# IO_PWR_FMU3_REV_G.net
KiCad netlist of a schematic drawn in Altium Designer
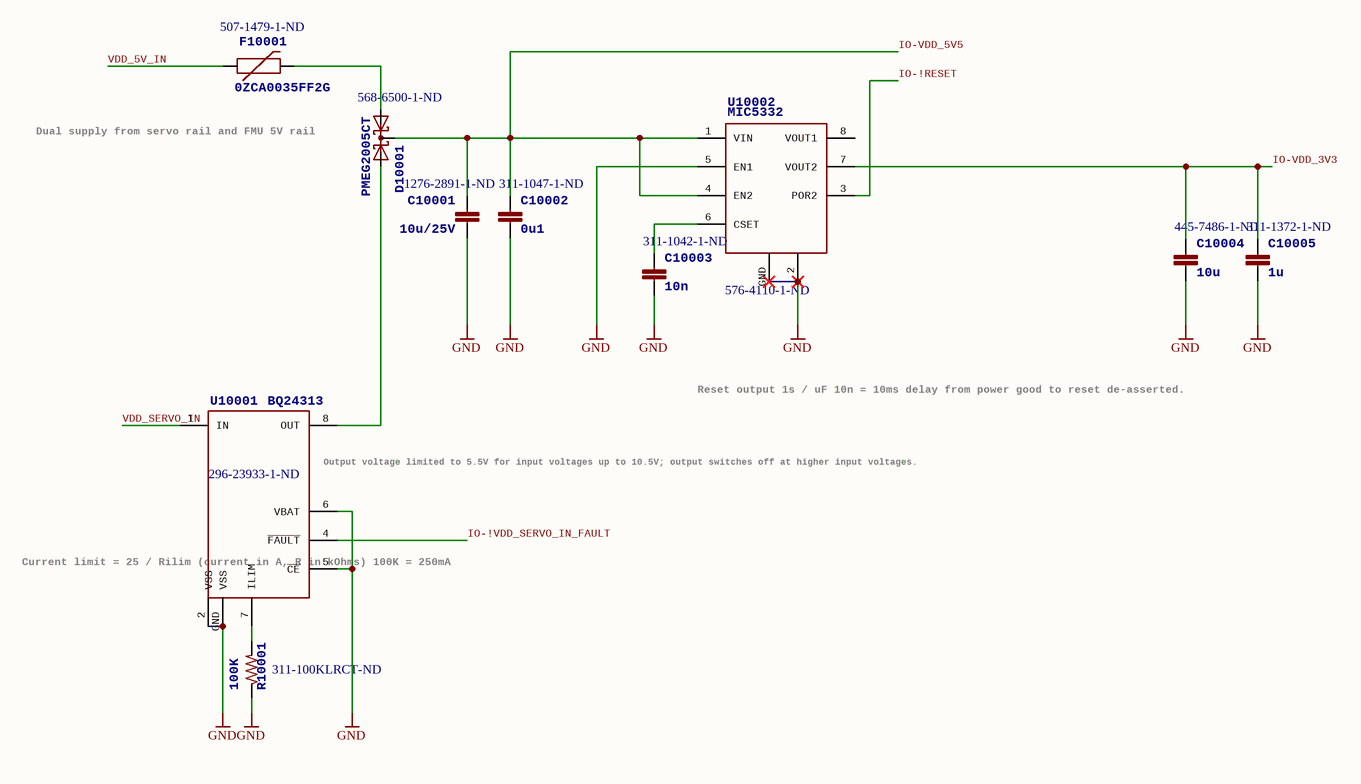
[diagram p0: IO_PWR_FMU3_REV_G.SchDoc]

(export (version "E")
  (design (tool "Eeschema 10.0.6"))
  (components
    (comp (ref "C10001")
      (value "10u/25V")
      (footprint "0805-CAP")
      (description "CAP CER 10UF 25V 10% X5R 0805")
      (fields
        (field (name "PARTNO") "CL21A106KAYNNNE")
        (field (name "SUPPLIER PART NUMBER 1") "1276-2891-1-ND")
        (field (name "3DR_PARTNO") "ECM0714")
      )
      (libsource (lib "pixhawk2") (part "CAP0805"))
    )
    (comp (ref "C10002")
      (value "0u1")
      (footprint "0402-CAP")
      (description "CAP CER 0.1UF 16V Y5V 0402")
      (fields
        (field (name "PARTNO") "CC0402ZRY5V7BB104")
        (field (name "SUPPLIER PART NUMBER 1") "311-1047-1-ND")
        (field (name "3DR_PARTNO") "ECM0700")
      )
      (libsource (lib "pixhawk2") (part "CAP0402"))
    )
    (comp (ref "C10003")
      (value "10n")
      (footprint "0402-CAP")
      (description "CAP CER 10000PF 16V 10% X7R 0402")
      (fields
        (field (name "PARTNO") "CC0402KRX7R7BB103")
        (field (name "SUPPLIER PART NUMBER 1") "311-1042-1-ND")
        (field (name "3DR_PARTNO") "ECM0711")
      )
      (libsource (lib "pixhawk2") (part "CAP0402"))
    )
    (comp (ref "C10004")
      (value "10u")
      (footprint "0603-CAP")
      (description "CAP CER 10UF 10V 10% X5R 0603")
      (fields
        (field (name "PARTNO") "C1608X5R1A106K080AC")
        (field (name "SUPPLIER PART NUMBER 1") "445-7486-1-ND")
        (field (name "3DR_PARTNO") "ECM0712")
      )
      (libsource (lib "pixhawk2") (part "CAP0603"))
    )
    (comp (ref "C10005")
      (value "1u")
      (footprint "0603-CAP")
      (description "CAP CER 1UF 16V Y5V 0603")
      (fields
        (field (name "PARTNO") "CC0603ZRY5V7BB105")
        (field (name "SUPPLIER PART NUMBER 1") "311-1372-1-ND")
        (field (name "3DR_PARTNO") "ECM0705")
      )
      (libsource (lib "pixhawk2") (part "CAP0603"))
    )
    (comp (ref "D10001")
      (value "PMEG2005CT")
      (footprint "SOT23-3")
      (description "DIODE SCHOTTKY 20V 500MA TO236AB")
      (fields (field (name "SUPPLIER PART NUMBER 1") "568-6500-1-ND") (field (name "3DR_PARTNO") "ECM0838"))
      (libsource (lib "pixhawk2") (part "PMEG2005CT"))
    )
    (comp (ref "F10001")
      (value "0ZCA0035FF2G")
      (footprint "PTC-1206")
      (description "PTC RESTTBLE 0.35A 16V CHIP 1206")
      (fields (field (name "SUPPLIER PART NUMBER 1") "507-1479-1-ND") (field (name "3DR_PARTNO") "ECM0802"))
      (libsource (lib "pixhawk2") (part "PTCSMD"))
    )
    (comp (ref "R10001")
      (value "100K")
      (footprint "0402-RES")
      (description "RES 100K OHM 1/16W 1% 0402 SMD")
      (fields
        (field (name "SUPPLIER PART NUMBER 1") "311-100KLRCT-ND")
        (field (name "3DR_PARTNO") "ECM0818")
        (field (name "PARTNO") "RC0402FR-07100KL")
      )
      (libsource (lib "pixhawk2") (part "RESISTOR0402-RES"))
    )
    (comp (ref "U10001")
      (value "BQ24313")
      (footprint "QFN8-DSG")
      (description "IC LI+ CHARGER FRONT END 8-SON")
      (fields
        (field (name "SUPPLIER PART NUMBER 1") "296-23933-1-ND")
        (field (name "3DR_PARTNO") "ECM0824")
        (field (name "PARTNO") "BQ24313DSGT")
      )
      (libsource (lib "pixhawk2") (part "BQ24313"))
    )
    (comp (ref "U10002")
      (value "MIC5332")
      (footprint "MLF-8-EPAD")
      (description "IC REG LDO 3.3V 0.3A 8TMLF")
      (fields
        (field (name "SUPPLIER PART NUMBER 1") "576-4110-1-ND")
        (field (name "3DR_PARTNO") "ECM0832")
        (field (name "PARTNO") "MIC5332-SSYMT TR")
      )
      (libsource (lib "pixhawk2") (part "MIC5332"))
    )
  )
  (nets
    (net (code "1") (name "/IO-!RESET") (class "Default")
      (node (ref "U10002") (pin "3") (pinfunction "POR2_3") (pintype "passive"))
    )
    (net (code "2") (name "/IO-!VDD_SERVO_IN_FAULT") (class "Default")
      (node (ref "U10001") (pin "4") (pinfunction "~{FAULT}_4") (pintype "passive"))
    )
    (net (code "3") (name "/IO-VDD_3V3") (class "Default")
      (node (ref "C10004") (pin "P$1") (pinfunction "1_P$1") (pintype "passive"))
      (node (ref "C10005") (pin "P$1") (pinfunction "1_P$1") (pintype "passive"))
      (node (ref "U10002") (pin "7") (pinfunction "VOUT2_7") (pintype "passive"))
    )
    (net (code "4") (name "/IO-VDD_5V5") (class "Default")
      (node (ref "C10001") (pin "P$1") (pinfunction "1_P$1") (pintype "passive"))
      (node (ref "C10002") (pin "P$1") (pinfunction "1_P$1") (pintype "passive"))
      (node (ref "D10001") (pin "3") (pinfunction "CC_3") (pintype "passive"))
      (node (ref "U10002") (pin "1") (pinfunction "VIN_1") (pintype "passive"))
      (node (ref "U10002") (pin "4") (pinfunction "EN2_4") (pintype "passive"))
    )
    (net (code "5") (name "/VDD_5V_IN") (class "Default")
      (node (ref "F10001") (pin "1") (pinfunction "1_1") (pintype "passive"))
    )
    (net (code "6") (name "/VDD_SERVO_IN") (class "Default")
      (node (ref "U10001") (pin "1") (pinfunction "IN_1") (pintype "passive"))
    )
    (net (code "7") (name "GND") (class "Default")
      (node (ref "C10001") (pin "P$2") (pinfunction "2_P$2") (pintype "passive"))
      (node (ref "C10002") (pin "P$2") (pinfunction "2_P$2") (pintype "passive"))
      (node (ref "C10003") (pin "P$2") (pinfunction "2_P$2") (pintype "passive"))
      (node (ref "C10004") (pin "P$2") (pinfunction "2_P$2") (pintype "passive"))
      (node (ref "C10005") (pin "P$2") (pinfunction "2_P$2") (pintype "passive"))
      (node (ref "R10001") (pin "P$1") (pinfunction "1_P$1") (pintype "passive"))
      (node (ref "U10001") (pin "2") (pinfunction "VSS_2") (pintype "passive"))
      (node (ref "U10001") (pin "5") (pinfunction "~{CE}_5") (pintype "passive"))
      (node (ref "U10001") (pin "6") (pinfunction "VBAT_6") (pintype "passive"))
      (node (ref "U10001") (pin "GND") (pinfunction "VSS_GND") (pintype "passive"))
      (node (ref "U10002") (pin "2") (pinfunction "GND_2") (pintype "power_in"))
      (node (ref "U10002") (pin "5") (pinfunction "EN1_5") (pintype "passive"))
      (node (ref "U10002") (pin "GND") (pinfunction "GND_GND") (pintype "power_in"))
    )
    (net (code "8") (name "Net-(C10003-1)") (class "Default")
      (node (ref "C10003") (pin "P$1") (pinfunction "1_P$1") (pintype "passive"))
      (node (ref "U10002") (pin "6") (pinfunction "CSET_6") (pintype "passive"))
    )
    (net (code "9") (name "Net-(D10001-A1)") (class "Default")
      (node (ref "D10001") (pin "1") (pinfunction "A1_1") (pintype "passive"))
      (node (ref "F10001") (pin "2") (pinfunction "2_2") (pintype "passive"))
    )
    (net (code "10") (name "Net-(D10001-A2)") (class "Default")
      (node (ref "D10001") (pin "2") (pinfunction "A2_2") (pintype "passive"))
      (node (ref "U10001") (pin "8") (pinfunction "OUT_8") (pintype "passive"))
    )
    (net (code "11") (name "Net-(R10001-2)") (class "Default")
      (node (ref "R10001") (pin "P$2") (pinfunction "2_P$2") (pintype "passive"))
      (node (ref "U10001") (pin "7") (pinfunction "ILIM_7") (pintype "passive"))
    )
    (net (code "12") (name "unconnected-(U10002-VOUT1-Pad8)") (class "Default")
      (node (ref "U10002") (pin "8") (pinfunction "VOUT1_8") (pintype "passive"))
    )
  )
)
